# project.net
KiCad netlist of a schematic drawn in EAGLE
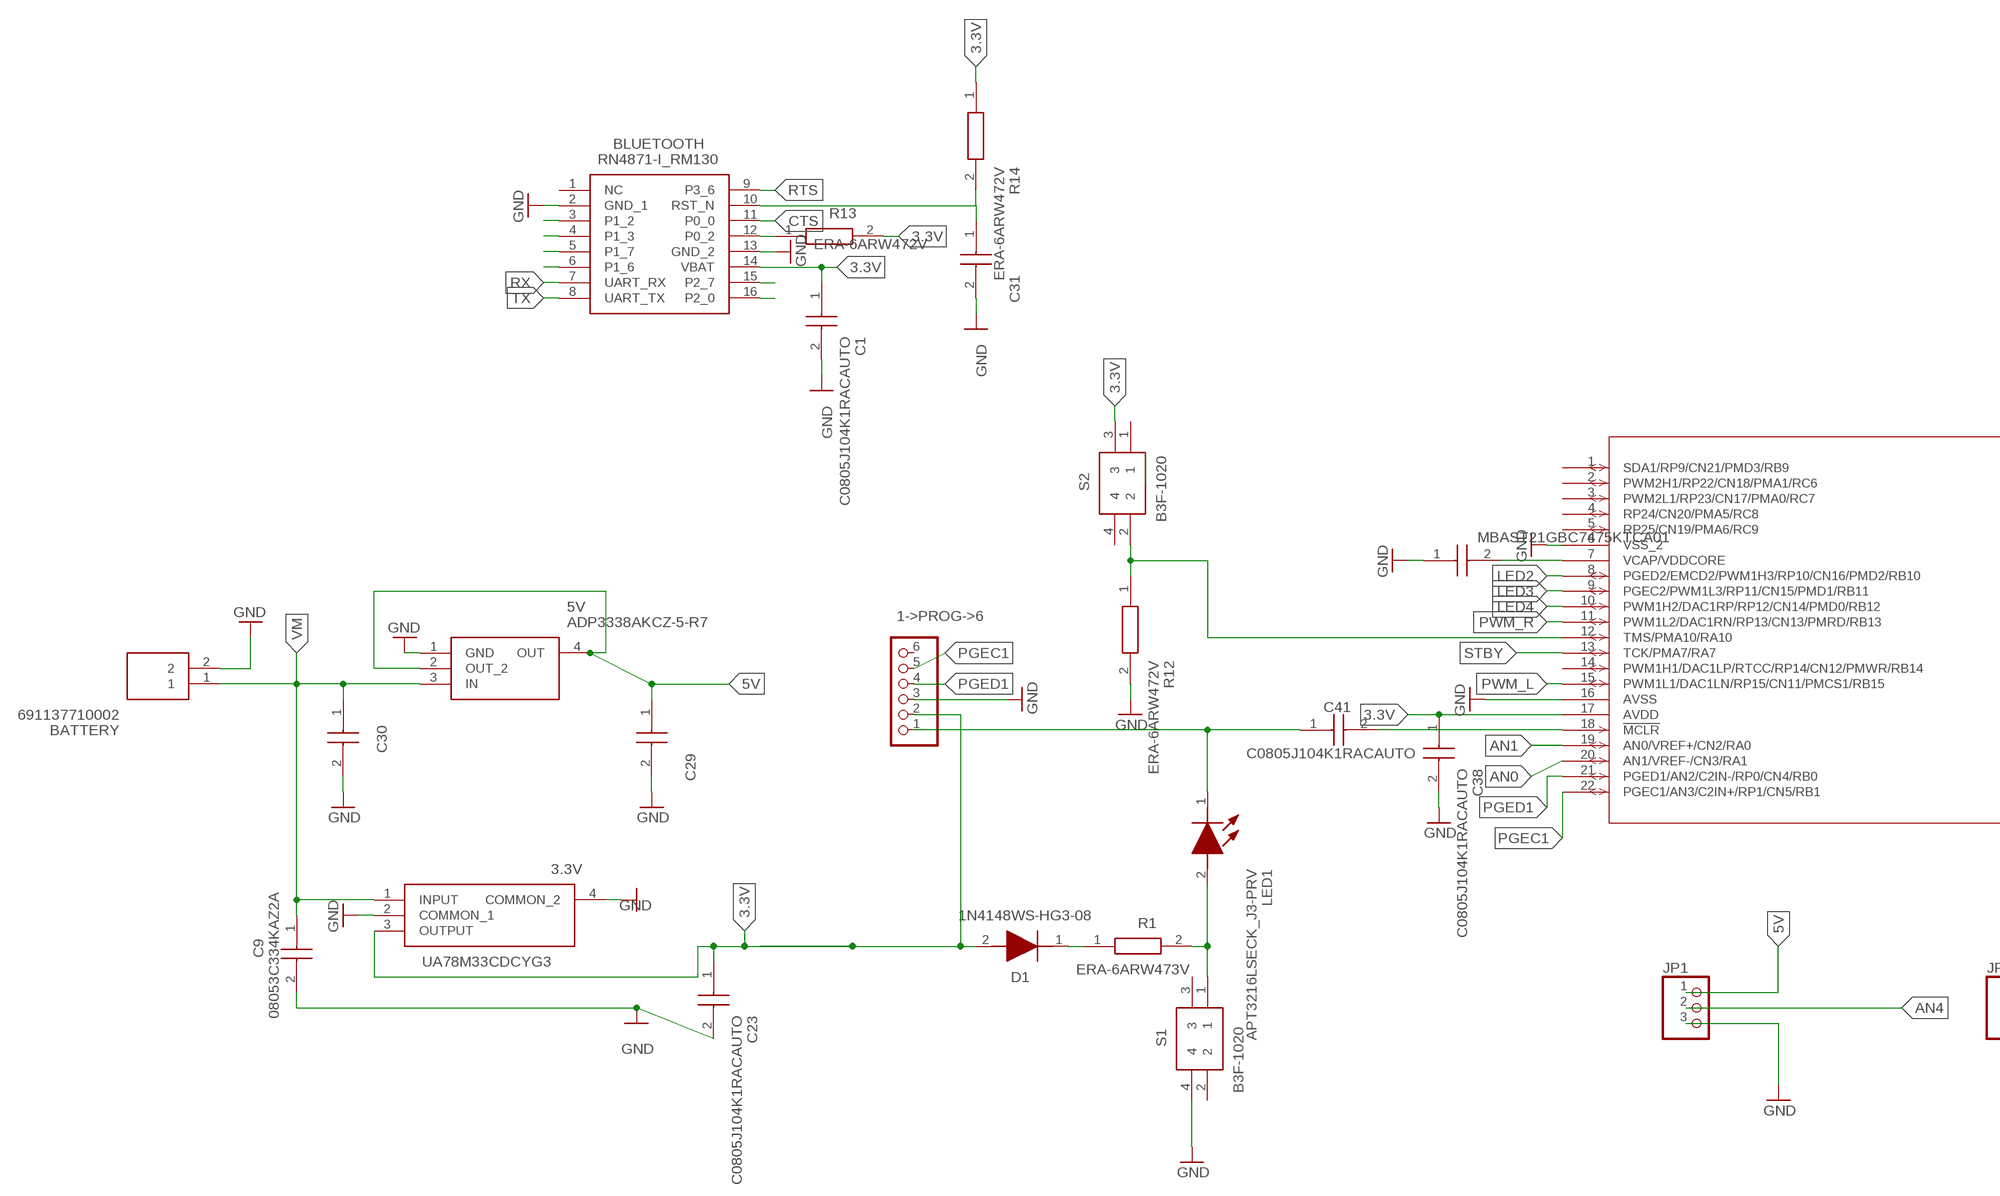
[diagram p0: schematic, sheet 1, part 1 of 2]
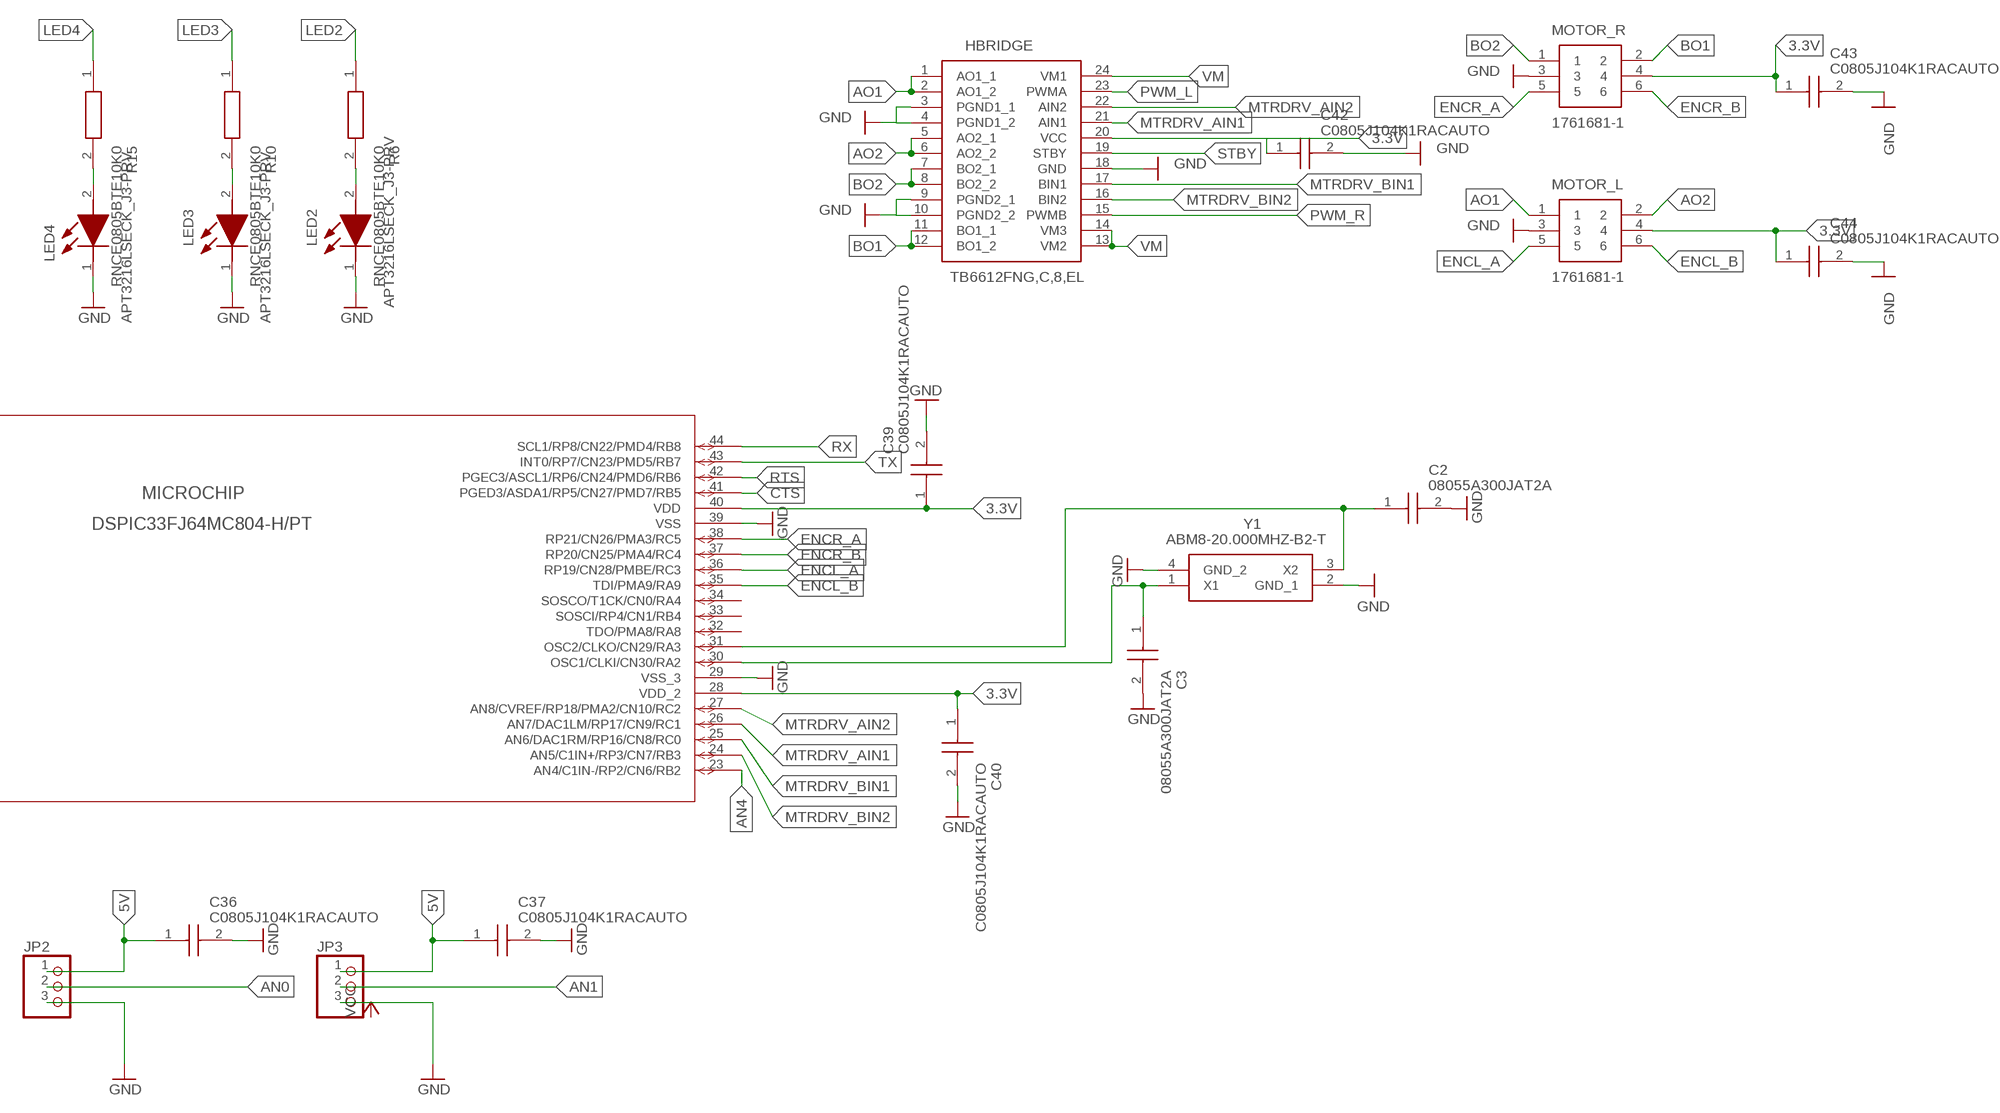
[diagram p1: schematic, sheet 1, part 2 of 2]

(export (version "E")
  (design (tool "Eeschema 10.0.6"))
  (components
    (comp (ref "1->PROG->6")
      (value "PINHD-1X6")
      (footprint "eagle-import:1X06")
      (libsource (lib "eagle-import") (part "PINHD-1X6"))
    )
    (comp (ref "3.3V")
      (value "UA78M33CDCYG3")
      (footprint "eagle-import:SOT230P700X180-4N")
      (fields (field (name "MOUSER_PART_NUMBER") "595-UA78M33CDCYG3"))
      (libsource (lib "eagle-import") (part "UA78M33CDCYG3"))
    )
    (comp (ref "5V")
      (value "ADP3338AKCZ-5-R7")
      (footprint "eagle-import:SOT230P700X180-4N")
      (fields (field (name "MOUSER_PART_NUMBER") "584-ADP3338AKCZ-5-R7"))
      (libsource (lib "eagle-import") (part "ADP3338AKCZ-5-R7"))
    )
    (comp (ref "BATTERY")
      (value "691137710002")
      (footprint "eagle-import:SHDR2W70P0X500_1X2_1000X750X11")
      (fields (field (name "MOUSER_PART_NUMBER") "710-691137710002"))
      (libsource (lib "eagle-import") (part "691137710002"))
    )
    (comp (ref "BLUETOOTH")
      (value "RN4871-I_RM130")
      (footprint "eagle-import:RN4871")
      (fields
        (field (name "MANUFACTURER_PART_NUMBER") "RN4871-I/RM130")
        (field (name "MOUSER_PART_NUMBER") "579-RN4871IRM130")
      )
      (libsource (lib "eagle-import") (part "RN4871-I_RM130"))
    )
    (comp (ref "C1")
      (value "C0805J104K1RACAUTO")
      (footprint "eagle-import:CAPC2012X140N")
      (libsource (lib "eagle-import") (part "C0805J104K1RACAUTO"))
    )
    (comp (ref "C2")
      (value "08055A300JAT2A")
      (footprint "eagle-import:CAPC2012X94N")
      (fields (field (name "MOUSER_PART_NUMBER") "581-08055A300J"))
      (libsource (lib "eagle-import") (part "08055A300JAT2A"))
    )
    (comp (ref "C3")
      (value "08055A300JAT2A")
      (footprint "eagle-import:CAPC2012X94N")
      (fields (field (name "MOUSER_PART_NUMBER") "581-08055A300J"))
      (libsource (lib "eagle-import") (part "08055A300JAT2A"))
    )
    (comp (ref "C4")
      (value "MBAST21GBC7475KTCA01")
      (footprint "eagle-import:CAPC2114X145N")
      (libsource (lib "eagle-import") (part "MBAST21GBC7475KTCA01"))
    )
    (comp (ref "C9")
      (value "08053C334KAZ2A")
      (footprint "eagle-import:CAPC2012X152N")
      (libsource (lib "eagle-import") (part "08053C334KAZ2A"))
    )
    (comp (ref "C23")
      (value "C0805J104K1RACAUTO")
      (footprint "eagle-import:CAPC2012X140N")
      (libsource (lib "eagle-import") (part "C0805J104K1RACAUTO"))
    )
    (comp (ref "C29")
      (value "C0805J104K1RACAUTO")
      (footprint "eagle-import:CAPC2012X140N")
      (libsource (lib "eagle-import") (part "C0805J104K1RACAUTO"))
    )
    (comp (ref "C30")
      (value "1µF")
      (footprint "eagle-import:CAPC2012X140N")
      (fields (field (name "MANUFACTURER_PART_NUMBER") "C0805J104K1RACAUTO"))
      (libsource (lib "eagle-import") (part "C0805J104K1RACAUTO"))
    )
    (comp (ref "C31")
      (value "C0805J104K1RACAUTO")
      (footprint "eagle-import:CAPC2012X140N")
      (libsource (lib "eagle-import") (part "C0805J104K1RACAUTO"))
    )
    (comp (ref "C36")
      (value "C0805J104K1RACAUTO")
      (footprint "eagle-import:CAPC2012X140N")
      (libsource (lib "eagle-import") (part "C0805J104K1RACAUTO"))
    )
    (comp (ref "C37")
      (value "C0805J104K1RACAUTO")
      (footprint "eagle-import:CAPC2012X140N")
      (libsource (lib "eagle-import") (part "C0805J104K1RACAUTO"))
    )
    (comp (ref "C38")
      (value "C0805J104K1RACAUTO")
      (footprint "eagle-import:CAPC2012X140N")
      (libsource (lib "eagle-import") (part "C0805J104K1RACAUTO"))
    )
    (comp (ref "C39")
      (value "C0805J104K1RACAUTO")
      (footprint "eagle-import:CAPC2012X140N")
      (libsource (lib "eagle-import") (part "C0805J104K1RACAUTO"))
    )
    (comp (ref "C40")
      (value "C0805J104K1RACAUTO")
      (footprint "eagle-import:CAPC2012X140N")
      (libsource (lib "eagle-import") (part "C0805J104K1RACAUTO"))
    )
    (comp (ref "C41")
      (value "C0805J104K1RACAUTO")
      (footprint "eagle-import:CAPC2012X140N")
      (libsource (lib "eagle-import") (part "C0805J104K1RACAUTO"))
    )
    (comp (ref "C42")
      (value "C0805J104K1RACAUTO")
      (footprint "eagle-import:CAPC2012X140N")
      (libsource (lib "eagle-import") (part "C0805J104K1RACAUTO"))
    )
    (comp (ref "C43")
      (value "C0805J104K1RACAUTO")
      (footprint "eagle-import:CAPC2012X140N")
      (libsource (lib "eagle-import") (part "C0805J104K1RACAUTO"))
    )
    (comp (ref "C44")
      (value "C0805J104K1RACAUTO")
      (footprint "eagle-import:CAPC2012X140N")
      (libsource (lib "eagle-import") (part "C0805J104K1RACAUTO"))
    )
    (comp (ref "D1")
      (value "1N4148WS-HG3-08")
      (footprint "eagle-import:SOD2713X115N")
      (fields (field (name "MOUSER_PART_NUMBER") "78-1N4148WS-HG3-08"))
      (libsource (lib "eagle-import") (part "1N4148WS-HG3-08"))
    )
    (comp (ref "HBRIDGE")
      (value "TB6612FNG,C,8,EL")
      (footprint "eagle-import:SOP65P760X160-24N")
      (fields (field (name "MOUSER_PART_NUMBER") "757-TB6612FNGC8EL"))
      (libsource (lib "eagle-import") (part "TB6612FNG,C,8,EL"))
    )
    (comp (ref "JP1")
      (value "PINHD-1X3")
      (footprint "eagle-import:1X03")
      (libsource (lib "eagle-import") (part "PINHD-1X3"))
    )
    (comp (ref "JP2")
      (value "PINHD-1X3")
      (footprint "eagle-import:1X03")
      (libsource (lib "eagle-import") (part "PINHD-1X3"))
    )
    (comp (ref "JP3")
      (value "PINHD-1X3")
      (footprint "eagle-import:1X03")
      (libsource (lib "eagle-import") (part "PINHD-1X3"))
    )
    (comp (ref "LED1")
      (value "APT3216LSECK_J3-PRV")
      (footprint "eagle-import:LEDC3216X95N")
      (fields
        (field (name "MANUFACTURER_PART_NUMBER") "APT3216LSECK/J3-PRV")
        (field (name "MOUSER_PART_NUMBER") "604-APT3216LSECKJ3RV")
      )
      (libsource (lib "eagle-import") (part "APT3216LSECK_J3-PRV"))
    )
    (comp (ref "LED2")
      (value "APT3216LSECK_J3-PRV")
      (footprint "eagle-import:LEDC3216X95N")
      (fields
        (field (name "MANUFACTURER_PART_NUMBER") "APT3216LSECK/J3-PRV")
        (field (name "MOUSER_PART_NUMBER") "604-APT3216LSECKJ3RV")
      )
      (libsource (lib "eagle-import") (part "APT3216LSECK_J3-PRV"))
    )
    (comp (ref "LED3")
      (value "APT3216LSECK_J3-PRV")
      (footprint "eagle-import:LEDC3216X95N")
      (fields
        (field (name "MANUFACTURER_PART_NUMBER") "APT3216LSECK/J3-PRV")
        (field (name "MOUSER_PART_NUMBER") "604-APT3216LSECKJ3RV")
      )
      (libsource (lib "eagle-import") (part "APT3216LSECK_J3-PRV"))
    )
    (comp (ref "LED4")
      (value "APT3216LSECK_J3-PRV")
      (footprint "eagle-import:LEDC3216X95N")
      (fields
        (field (name "MANUFACTURER_PART_NUMBER") "APT3216LSECK/J3-PRV")
        (field (name "MOUSER_PART_NUMBER") "604-APT3216LSECKJ3RV")
      )
      (libsource (lib "eagle-import") (part "APT3216LSECK_J3-PRV"))
    )
    (comp (ref "MICROCHIP")
      (value "DSPIC33FJ64MC804-H/PT")
      (footprint "eagle-import:TQFP44_10X10MC_MCH")
      (fields (field (name "COPYRIGHT") "Copyright (C) 2025 Ultra Librarian. All rights reserved."))
      (libsource (lib "eagle-import") (part "DSPIC33FJ64MC804-H/PT"))
    )
    (comp (ref "MOTOR_L")
      (value "1761681-1")
      (footprint "eagle-import:SHDR6W67P254_2X3_1524X916X922P")
      (fields (field (name "MOUSER_PART_NUMBER") "571-1761681-1"))
      (libsource (lib "eagle-import") (part "1761681-1"))
    )
    (comp (ref "MOTOR_R")
      (value "1761681-1")
      (footprint "eagle-import:SHDR6W67P254_2X3_1524X916X922P")
      (fields (field (name "MOUSER_PART_NUMBER") "571-1761681-1"))
      (libsource (lib "eagle-import") (part "1761681-1"))
    )
    (comp (ref "R1")
      (value "ERA-6ARW473V")
      (footprint "eagle-import:ERA6AEB101V")
      (fields (field (name "MOUSER_PART_NUMBER") "667-ERA-6ARW473V"))
      (libsource (lib "eagle-import") (part "ERA-6ARW473V"))
    )
    (comp (ref "R6")
      (value "RNCE0805BTE10K0")
      (footprint "eagle-import:RESC2012X65N")
      (libsource (lib "eagle-import") (part "RNCE0805BTE10K0"))
    )
    (comp (ref "R10")
      (value "RNCE0805BTE10K0")
      (footprint "eagle-import:RESC2012X65N")
      (libsource (lib "eagle-import") (part "RNCE0805BTE10K0"))
    )
    (comp (ref "R12")
      (value "ERA-6ARW472V")
      (footprint "eagle-import:ERA6AEB101V")
      (fields (field (name "MOUSER_PART_NUMBER") "667-ERA-6ARW472V"))
      (libsource (lib "eagle-import") (part "ERA-6ARW472V"))
    )
    (comp (ref "R13")
      (value "ERA-6ARW472V")
      (footprint "eagle-import:ERA6AEB101V")
      (fields (field (name "MOUSER_PART_NUMBER") "667-ERA-6ARW472V"))
      (libsource (lib "eagle-import") (part "ERA-6ARW472V"))
    )
    (comp (ref "R14")
      (value "ERA-6ARW472V")
      (footprint "eagle-import:ERA6AEB101V")
      (fields (field (name "MOUSER_PART_NUMBER") "667-ERA-6ARW472V"))
      (libsource (lib "eagle-import") (part "ERA-6ARW472V"))
    )
    (comp (ref "R15")
      (value "RNCE0805BTE10K0")
      (footprint "eagle-import:RESC2012X65N")
      (libsource (lib "eagle-import") (part "RNCE0805BTE10K0"))
    )
    (comp (ref "S1")
      (value "B3F-1020")
      (footprint "eagle-import:B3F1000")
      (fields (field (name "MOUSER_PART_NUMBER") "653-B3F-1020"))
      (libsource (lib "eagle-import") (part "B3F-1020"))
    )
    (comp (ref "S2")
      (value "B3F-1020")
      (footprint "eagle-import:B3F1000")
      (fields (field (name "MOUSER_PART_NUMBER") "653-B3F-1020"))
      (libsource (lib "eagle-import") (part "B3F-1020"))
    )
    (comp (ref "Y1")
      (value "ABM8-20.000MHZ-B2-T")
      (footprint "eagle-import:ABM810000MHZ12D2W")
      (fields (field (name "MOUSER_PART_NUMBER") "815-ABM8-20-B2-T"))
      (libsource (lib "eagle-import") (part "ABM8-20.000MHZ-B2-T"))
    )
  )
  (nets
    (net (code "1") (name "3.3V") (class "Default")
      (node (ref "1->PROG->6") (pin "2") (pinfunction "2_2") (pintype "passive"))
      (node (ref "3.3V") (pin "3") (pinfunction "OUTPUT_3") (pintype "bidirectional"))
      (node (ref "BLUETOOTH") (pin "14") (pinfunction "VBAT_14") (pintype "bidirectional"))
      (node (ref "C1") (pin "1") (pinfunction "1_1") (pintype "bidirectional"))
      (node (ref "C23") (pin "1") (pinfunction "1_1") (pintype "bidirectional"))
      (node (ref "C38") (pin "1") (pinfunction "1_1") (pintype "bidirectional"))
      (node (ref "C39") (pin "1") (pinfunction "1_1") (pintype "bidirectional"))
      (node (ref "C40") (pin "1") (pinfunction "1_1") (pintype "bidirectional"))
      (node (ref "C42") (pin "1") (pinfunction "1_1") (pintype "bidirectional"))
      (node (ref "C43") (pin "1") (pinfunction "1_1") (pintype "bidirectional"))
      (node (ref "C44") (pin "1") (pinfunction "1_1") (pintype "bidirectional"))
      (node (ref "D1") (pin "2") (pinfunction "A_2") (pintype "bidirectional"))
      (node (ref "HBRIDGE") (pin "20") (pinfunction "VCC_20") (pintype "bidirectional"))
      (node (ref "MICROCHIP") (pin "17") (pinfunction "AVDD_17") (pintype "power_in"))
      (node (ref "MICROCHIP") (pin "28") (pinfunction "VDD_2_28") (pintype "power_in"))
      (node (ref "MICROCHIP") (pin "40") (pinfunction "VDD_40") (pintype "power_in"))
      (node (ref "MOTOR_L") (pin "4") (pinfunction "4_4") (pintype "bidirectional"))
      (node (ref "MOTOR_R") (pin "4") (pinfunction "4_4") (pintype "bidirectional"))
      (node (ref "R13") (pin "2") (pinfunction "2_2") (pintype "bidirectional"))
      (node (ref "R14") (pin "1") (pinfunction "1_1") (pintype "bidirectional"))
      (node (ref "S2") (pin "3") (pinfunction "3_3") (pintype "bidirectional"))
    )
    (net (code "2") (name "5V") (class "Default")
      (node (ref "5V") (pin "2") (pinfunction "OUT_2_2") (pintype "bidirectional"))
      (node (ref "5V") (pin "4") (pinfunction "OUT_4") (pintype "bidirectional"))
      (node (ref "C29") (pin "1") (pinfunction "1_1") (pintype "bidirectional"))
      (node (ref "C36") (pin "1") (pinfunction "1_1") (pintype "bidirectional"))
      (node (ref "C37") (pin "1") (pinfunction "1_1") (pintype "bidirectional"))
      (node (ref "JP1") (pin "1") (pinfunction "1_1") (pintype "passive"))
      (node (ref "JP2") (pin "1") (pinfunction "1_1") (pintype "passive"))
      (node (ref "JP3") (pin "1") (pinfunction "1_1") (pintype "passive"))
    )
    (net (code "3") (name "AN0") (class "Default")
      (node (ref "JP2") (pin "2") (pinfunction "2_2") (pintype "passive"))
      (node (ref "MICROCHIP") (pin "20") (pinfunction "AN1/VREF-/CN3/RA1_20") (pintype "bidirectional"))
    )
    (net (code "4") (name "AN1") (class "Default")
      (node (ref "JP3") (pin "2") (pinfunction "2_2") (pintype "passive"))
      (node (ref "MICROCHIP") (pin "19") (pinfunction "AN0/VREF+/CN2/RA0_19") (pintype "bidirectional"))
    )
    (net (code "5") (name "AN4") (class "Default")
      (node (ref "JP1") (pin "2") (pinfunction "2_2") (pintype "passive"))
      (node (ref "MICROCHIP") (pin "23") (pinfunction "AN4/C1IN-/RP2/CN6/RB2_23") (pintype "bidirectional"))
    )
    (net (code "6") (name "AO1") (class "Default")
      (node (ref "HBRIDGE") (pin "1") (pinfunction "AO1_1_1") (pintype "bidirectional"))
      (node (ref "HBRIDGE") (pin "2") (pinfunction "AO1_2_2") (pintype "bidirectional"))
      (node (ref "MOTOR_L") (pin "1") (pinfunction "1_1") (pintype "bidirectional"))
    )
    (net (code "7") (name "AO2") (class "Default")
      (node (ref "HBRIDGE") (pin "5") (pinfunction "AO2_1_5") (pintype "bidirectional"))
      (node (ref "HBRIDGE") (pin "6") (pinfunction "AO2_2_6") (pintype "bidirectional"))
      (node (ref "MOTOR_L") (pin "2") (pinfunction "2_2") (pintype "bidirectional"))
    )
    (net (code "8") (name "BO1") (class "Default")
      (node (ref "HBRIDGE") (pin "11") (pinfunction "BO1_1_11") (pintype "bidirectional"))
      (node (ref "HBRIDGE") (pin "12") (pinfunction "BO1_2_12") (pintype "bidirectional"))
      (node (ref "MOTOR_R") (pin "2") (pinfunction "2_2") (pintype "bidirectional"))
    )
    (net (code "9") (name "BO2") (class "Default")
      (node (ref "HBRIDGE") (pin "7") (pinfunction "BO2_1_7") (pintype "bidirectional"))
      (node (ref "HBRIDGE") (pin "8") (pinfunction "BO2_2_8") (pintype "bidirectional"))
      (node (ref "MOTOR_R") (pin "1") (pinfunction "1_1") (pintype "bidirectional"))
    )
    (net (code "10") (name "CTS") (class "Default")
      (node (ref "BLUETOOTH") (pin "11") (pinfunction "P0_0_11") (pintype "bidirectional"))
      (node (ref "MICROCHIP") (pin "41") (pinfunction "PGED3/ASDA1/RP5/CN27/PMD7/RB5_41") (pintype "bidirectional"))
    )
    (net (code "11") (name "ENCL_A") (class "Default")
      (node (ref "MICROCHIP") (pin "36") (pinfunction "RP19/CN28/PMBE/RC3_36") (pintype "bidirectional"))
      (node (ref "MOTOR_L") (pin "5") (pinfunction "5_5") (pintype "bidirectional"))
    )
    (net (code "12") (name "ENCL_B") (class "Default")
      (node (ref "MICROCHIP") (pin "35") (pinfunction "TDI/PMA9/RA9_35") (pintype "bidirectional"))
      (node (ref "MOTOR_L") (pin "6") (pinfunction "6_6") (pintype "bidirectional"))
    )
    (net (code "13") (name "ENCR_A") (class "Default")
      (node (ref "MICROCHIP") (pin "38") (pinfunction "RP21/CN26/PMA3/RC5_38") (pintype "bidirectional"))
      (node (ref "MOTOR_R") (pin "5") (pinfunction "5_5") (pintype "bidirectional"))
    )
    (net (code "14") (name "ENCR_B") (class "Default")
      (node (ref "MICROCHIP") (pin "37") (pinfunction "RP20/CN25/PMA4/RC4_37") (pintype "bidirectional"))
      (node (ref "MOTOR_R") (pin "6") (pinfunction "6_6") (pintype "bidirectional"))
    )
    (net (code "15") (name "GND") (class "Default")
      (node (ref "1->PROG->6") (pin "3") (pinfunction "3_3") (pintype "passive"))
      (node (ref "3.3V") (pin "2") (pinfunction "COMMON_1_2") (pintype "bidirectional"))
      (node (ref "3.3V") (pin "4") (pinfunction "COMMON_2_4") (pintype "bidirectional"))
      (node (ref "5V") (pin "1") (pinfunction "GND_1") (pintype "bidirectional"))
      (node (ref "BATTERY") (pin "2") (pinfunction "2_2") (pintype "bidirectional"))
      (node (ref "BLUETOOTH") (pin "13") (pinfunction "GND_2_13") (pintype "bidirectional"))
      (node (ref "BLUETOOTH") (pin "2") (pinfunction "GND_1_2") (pintype "bidirectional"))
      (node (ref "C1") (pin "2") (pinfunction "2_2") (pintype "bidirectional"))
      (node (ref "C2") (pin "2") (pinfunction "2_2") (pintype "bidirectional"))
      (node (ref "C23") (pin "2") (pinfunction "2_2") (pintype "bidirectional"))
      (node (ref "C29") (pin "2") (pinfunction "2_2") (pintype "bidirectional"))
      (node (ref "C3") (pin "2") (pinfunction "2_2") (pintype "bidirectional"))
      (node (ref "C30") (pin "2") (pinfunction "2_2") (pintype "bidirectional"))
      (node (ref "C31") (pin "2") (pinfunction "2_2") (pintype "bidirectional"))
      (node (ref "C36") (pin "2") (pinfunction "2_2") (pintype "bidirectional"))
      (node (ref "C37") (pin "2") (pinfunction "2_2") (pintype "bidirectional"))
      (node (ref "C38") (pin "2") (pinfunction "2_2") (pintype "bidirectional"))
      (node (ref "C39") (pin "2") (pinfunction "2_2") (pintype "bidirectional"))
      (node (ref "C4") (pin "1") (pinfunction "1_1") (pintype "bidirectional"))
      (node (ref "C40") (pin "2") (pinfunction "2_2") (pintype "bidirectional"))
      (node (ref "C42") (pin "2") (pinfunction "2_2") (pintype "bidirectional"))
      (node (ref "C43") (pin "2") (pinfunction "2_2") (pintype "bidirectional"))
      (node (ref "C44") (pin "2") (pinfunction "2_2") (pintype "bidirectional"))
      (node (ref "C9") (pin "2") (pinfunction "2_2") (pintype "bidirectional"))
      (node (ref "HBRIDGE") (pin "10") (pinfunction "PGND2_2_10") (pintype "bidirectional"))
      (node (ref "HBRIDGE") (pin "18") (pinfunction "GND_18") (pintype "bidirectional"))
      (node (ref "HBRIDGE") (pin "3") (pinfunction "PGND1_1_3") (pintype "bidirectional"))
      (node (ref "HBRIDGE") (pin "4") (pinfunction "PGND1_2_4") (pintype "bidirectional"))
      (node (ref "HBRIDGE") (pin "9") (pinfunction "PGND2_1_9") (pintype "bidirectional"))
      (node (ref "JP1") (pin "3") (pinfunction "3_3") (pintype "passive"))
      (node (ref "JP2") (pin "3") (pinfunction "3_3") (pintype "passive"))
      (node (ref "JP3") (pin "3") (pinfunction "3_3") (pintype "passive"))
      (node (ref "LED2") (pin "1") (pinfunction "K_1") (pintype "bidirectional"))
      (node (ref "LED3") (pin "1") (pinfunction "K_1") (pintype "bidirectional"))
      (node (ref "LED4") (pin "1") (pinfunction "K_1") (pintype "bidirectional"))
      (node (ref "MICROCHIP") (pin "16") (pinfunction "AVSS_16") (pintype "power_in"))
      (node (ref "MICROCHIP") (pin "29") (pinfunction "VSS_3_29") (pintype "power_in"))
      (node (ref "MICROCHIP") (pin "39") (pinfunction "VSS_39") (pintype "power_in"))
      (node (ref "MICROCHIP") (pin "6") (pinfunction "VSS_2_6") (pintype "power_in"))
      (node (ref "MOTOR_L") (pin "3") (pinfunction "3_3") (pintype "bidirectional"))
      (node (ref "MOTOR_R") (pin "3") (pinfunction "3_3") (pintype "bidirectional"))
      (node (ref "R12") (pin "2") (pinfunction "2_2") (pintype "bidirectional"))
      (node (ref "S1") (pin "4") (pinfunction "4_4") (pintype "bidirectional"))
      (node (ref "Y1") (pin "2") (pinfunction "GND_1_2") (pintype "bidirectional"))
      (node (ref "Y1") (pin "4") (pinfunction "GND_2_4") (pintype "bidirectional"))
    )
    (net (code "16") (name "LED2") (class "Default")
      (node (ref "MICROCHIP") (pin "8") (pinfunction "PGED2/EMCD2/PWM1H3/RP10/CN16/PMD2/RB10_8") (pintype "bidirectional"))
      (node (ref "R6") (pin "1") (pinfunction "1_1") (pintype "bidirectional"))
    )
    (net (code "17") (name "LED3") (class "Default")
      (node (ref "MICROCHIP") (pin "9") (pinfunction "PGEC2/PWM1L3/RP11/CN15/PMD1/RB11_9") (pintype "bidirectional"))
      (node (ref "R10") (pin "1") (pinfunction "1_1") (pintype "bidirectional"))
    )
    (net (code "18") (name "LED4") (class "Default")
      (node (ref "MICROCHIP") (pin "10") (pinfunction "PWM1H2/DAC1RP/RP12/CN14/PMD0/RB12_10") (pintype "bidirectional"))
      (node (ref "R15") (pin "1") (pinfunction "1_1") (pintype "bidirectional"))
    )
    (net (code "19") (name "MTRDRV_AIN1") (class "Default")
      (node (ref "HBRIDGE") (pin "21") (pinfunction "AIN1_21") (pintype "bidirectional"))
      (node (ref "MICROCHIP") (pin "26") (pinfunction "AN7/DAC1LM/RP17/CN9/RC1_26") (pintype "bidirectional"))
    )
    (net (code "20") (name "MTRDRV_AIN2") (class "Default")
      (node (ref "HBRIDGE") (pin "22") (pinfunction "AIN2_22") (pintype "bidirectional"))
      (node (ref "MICROCHIP") (pin "27") (pinfunction "AN8/CVREF/RP18/PMA2/CN10/RC2_27") (pintype "bidirectional"))
    )
    (net (code "21") (name "MTRDRV_BIN1") (class "Default")
      (node (ref "HBRIDGE") (pin "17") (pinfunction "BIN1_17") (pintype "bidirectional"))
      (node (ref "MICROCHIP") (pin "25") (pinfunction "AN6/DAC1RM/RP16/CN8/RC0_25") (pintype "bidirectional"))
    )
    (net (code "22") (name "MTRDRV_BIN2") (class "Default")
      (node (ref "HBRIDGE") (pin "16") (pinfunction "BIN2_16") (pintype "bidirectional"))
      (node (ref "MICROCHIP") (pin "24") (pinfunction "AN5/C1IN+/RP3/CN7/RB3_24") (pintype "bidirectional"))
    )
    (net (code "23") (name "Net-(BLUETOOTH-P0_2)") (class "Default")
      (node (ref "BLUETOOTH") (pin "12") (pinfunction "P0_2_12") (pintype "bidirectional"))
      (node (ref "R13") (pin "1") (pinfunction "1_1") (pintype "bidirectional"))
    )
    (net (code "24") (name "Net-(BLUETOOTH-RST_N)") (class "Default")
      (node (ref "BLUETOOTH") (pin "10") (pinfunction "RST_N_10") (pintype "bidirectional"))
      (node (ref "C31") (pin "1") (pinfunction "1_1") (pintype "bidirectional"))
      (node (ref "R14") (pin "2") (pinfunction "2_2") (pintype "bidirectional"))
    )
    (net (code "25") (name "Net-(D1-K)") (class "Default")
      (node (ref "D1") (pin "1") (pinfunction "K_1") (pintype "bidirectional"))
      (node (ref "R1") (pin "1") (pinfunction "1_1") (pintype "bidirectional"))
    )
    (net (code "26") (name "Net-(LED1-A)") (class "Default")
      (node (ref "LED1") (pin "2") (pinfunction "A_2") (pintype "bidirectional"))
      (node (ref "R1") (pin "2") (pinfunction "2_2") (pintype "bidirectional"))
      (node (ref "S1") (pin "1") (pinfunction "1_1") (pintype "bidirectional"))
    )
    (net (code "27") (name "Net-(LED1-K)") (class "Default")
      (node (ref "1->PROG->6") (pin "1") (pinfunction "1_1") (pintype "passive"))
      (node (ref "C41") (pin "1") (pinfunction "1_1") (pintype "bidirectional"))
      (node (ref "LED1") (pin "1") (pinfunction "K_1") (pintype "bidirectional"))
    )
    (net (code "28") (name "Net-(LED2-A)") (class "Default")
      (node (ref "LED2") (pin "2") (pinfunction "A_2") (pintype "bidirectional"))
      (node (ref "R6") (pin "2") (pinfunction "2_2") (pintype "bidirectional"))
    )
    (net (code "29") (name "Net-(LED3-A)") (class "Default")
      (node (ref "LED3") (pin "2") (pinfunction "A_2") (pintype "bidirectional"))
      (node (ref "R10") (pin "2") (pinfunction "2_2") (pintype "bidirectional"))
    )
    (net (code "30") (name "Net-(LED4-A)") (class "Default")
      (node (ref "LED4") (pin "2") (pinfunction "A_2") (pintype "bidirectional"))
      (node (ref "R15") (pin "2") (pinfunction "2_2") (pintype "bidirectional"))
    )
    (net (code "31") (name "Net-(MICROCHIP-OSC1{slash}CLKI{slash}CN30{slash}RA2)") (class "Default")
      (node (ref "C3") (pin "1") (pinfunction "1_1") (pintype "bidirectional"))
      (node (ref "MICROCHIP") (pin "30") (pinfunction "OSC1/CLKI/CN30/RA2_30") (pintype "bidirectional"))
      (node (ref "Y1") (pin "1") (pinfunction "X1_1") (pintype "bidirectional"))
    )
    (net (code "32") (name "Net-(MICROCHIP-OSC2{slash}CLKO{slash}CN29{slash}RA3)") (class "Default")
      (node (ref "C2") (pin "1") (pinfunction "1_1") (pintype "bidirectional"))
      (node (ref "MICROCHIP") (pin "31") (pinfunction "OSC2/CLKO/CN29/RA3_31") (pintype "bidirectional"))
      (node (ref "Y1") (pin "3") (pinfunction "X2_3") (pintype "bidirectional"))
    )
    (net (code "33") (name "Net-(MICROCHIP-TMS{slash}PMA10{slash}RA10)") (class "Default")
      (node (ref "MICROCHIP") (pin "12") (pinfunction "TMS/PMA10/RA10_12") (pintype "bidirectional"))
      (node (ref "R12") (pin "1") (pinfunction "1_1") (pintype "bidirectional"))
      (node (ref "S2") (pin "2") (pinfunction "2_2") (pintype "bidirectional"))
    )
    (net (code "34") (name "Net-(MICROCHIP-VCAP{slash}VDDCORE)") (class "Default")
      (node (ref "C4") (pin "2") (pinfunction "2_2") (pintype "bidirectional"))
      (node (ref "MICROCHIP") (pin "7") (pinfunction "VCAP/VDDCORE_7") (pintype "power_in"))
    )
    (net (code "35") (name "Net-(MICROCHIP-~{MCLR})") (class "Default")
      (node (ref "C41") (pin "2") (pinfunction "2_2") (pintype "bidirectional"))
      (node (ref "MICROCHIP") (pin "18") (pinfunction "~{MCLR}_18") (pintype "input"))
    )
    (net (code "36") (name "PGEC1") (class "Default")
      (node (ref "1->PROG->6") (pin "5") (pinfunction "5_5") (pintype "passive"))
      (node (ref "MICROCHIP") (pin "22") (pinfunction "PGEC1/AN3/C2IN+/RP1/CN5/RB1_22") (pintype "bidirectional"))
    )
    (net (code "37") (name "PGED1") (class "Default")
      (node (ref "1->PROG->6") (pin "4") (pinfunction "4_4") (pintype "passive"))
      (node (ref "MICROCHIP") (pin "21") (pinfunction "PGED1/AN2/C2IN-/RP0/CN4/RB0_21") (pintype "bidirectional"))
    )
    (net (code "38") (name "PWM_L") (class "Default")
      (node (ref "HBRIDGE") (pin "23") (pinfunction "PWMA_23") (pintype "bidirectional"))
      (node (ref "MICROCHIP") (pin "15") (pinfunction "PWM1L1/DAC1LN/RP15/CN11/PMCS1/RB15_15") (pintype "bidirectional"))
    )
    (net (code "39") (name "PWM_R") (class "Default")
      (node (ref "HBRIDGE") (pin "15") (pinfunction "PWMB_15") (pintype "bidirectional"))
      (node (ref "MICROCHIP") (pin "11") (pinfunction "PWM1L2/DAC1RN/RP13/CN13/PMRD/RB13_11") (pintype "bidirectional"))
    )
    (net (code "40") (name "RTS") (class "Default")
      (node (ref "BLUETOOTH") (pin "9") (pinfunction "P3_6_9") (pintype "bidirectional"))
      (node (ref "MICROCHIP") (pin "42") (pinfunction "PGEC3/ASCL1/RP6/CN24/PMD6/RB6_42") (pintype "bidirectional"))
    )
    (net (code "41") (name "RX") (class "Default")
      (node (ref "BLUETOOTH") (pin "7") (pinfunction "UART_RX_7") (pintype "bidirectional"))
      (node (ref "MICROCHIP") (pin "44") (pinfunction "SCL1/RP8/CN22/PMD4/RB8_44") (pintype "bidirectional"))
    )
    (net (code "42") (name "STBY") (class "Default")
      (node (ref "HBRIDGE") (pin "19") (pinfunction "STBY_19") (pintype "bidirectional"))
      (node (ref "MICROCHIP") (pin "13") (pinfunction "TCK/PMA7/RA7_13") (pintype "bidirectional"))
    )
    (net (code "43") (name "TX") (class "Default")
      (node (ref "BLUETOOTH") (pin "8") (pinfunction "UART_TX_8") (pintype "bidirectional"))
      (node (ref "MICROCHIP") (pin "43") (pinfunction "INT0/RP7/CN23/PMD5/RB7_43") (pintype "bidirectional"))
    )
    (net (code "45") (name "VM") (class "Default")
      (node (ref "3.3V") (pin "1") (pinfunction "INPUT_1") (pintype "bidirectional"))
      (node (ref "5V") (pin "3") (pinfunction "IN_3") (pintype "bidirectional"))
      (node (ref "BATTERY") (pin "1") (pinfunction "1_1") (pintype "bidirectional"))
      (node (ref "C30") (pin "1") (pinfunction "1_1") (pintype "bidirectional"))
      (node (ref "C9") (pin "1") (pinfunction "1_1") (pintype "bidirectional"))
      (node (ref "HBRIDGE") (pin "13") (pinfunction "VM2_13") (pintype "bidirectional"))
      (node (ref "HBRIDGE") (pin "14") (pinfunction "VM3_14") (pintype "bidirectional"))
      (node (ref "HBRIDGE") (pin "24") (pinfunction "VM1_24") (pintype "bidirectional"))
    )
    (net (code "46") (name "unconnected-(1->PROG->6-Pad6)") (class "Default")
      (node (ref "1->PROG->6") (pin "6") (pinfunction "6_6") (pintype "passive"))
    )
    (net (code "47") (name "unconnected-(BLUETOOTH-NC-Pad1)") (class "Default")
      (node (ref "BLUETOOTH") (pin "1") (pinfunction "NC_1") (pintype "no_connect"))
    )
    (net (code "48") (name "unconnected-(BLUETOOTH-P1_2-Pad3)") (class "Default")
      (node (ref "BLUETOOTH") (pin "3") (pinfunction "P1_2_3") (pintype "bidirectional"))
    )
    (net (code "49") (name "unconnected-(BLUETOOTH-P1_3-Pad4)") (class "Default")
      (node (ref "BLUETOOTH") (pin "4") (pinfunction "P1_3_4") (pintype "bidirectional"))
    )
    (net (code "50") (name "unconnected-(BLUETOOTH-P1_6-Pad6)") (class "Default")
      (node (ref "BLUETOOTH") (pin "6") (pinfunction "P1_6_6") (pintype "bidirectional"))
    )
    (net (code "51") (name "unconnected-(BLUETOOTH-P1_7-Pad5)") (class "Default")
      (node (ref "BLUETOOTH") (pin "5") (pinfunction "P1_7_5") (pintype "bidirectional"))
    )
    (net (code "52") (name "unconnected-(BLUETOOTH-P2_0-Pad16)") (class "Default")
      (node (ref "BLUETOOTH") (pin "16") (pinfunction "P2_0_16") (pintype "bidirectional"))
    )
    (net (code "53") (name "unconnected-(BLUETOOTH-P2_7-Pad15)") (class "Default")
      (node (ref "BLUETOOTH") (pin "15") (pinfunction "P2_7_15") (pintype "bidirectional"))
    )
    (net (code "54") (name "unconnected-(MICROCHIP-PWM1H1{slash}DAC1LP{slash}RTCC{slash}RP14{slash}CN12{slash}PMWR{slash}RB14-Pad14)") (class "Default")
      (node (ref "MICROCHIP") (pin "14") (pinfunction "PWM1H1/DAC1LP/RTCC/RP14/CN12/PMWR/RB14_14") (pintype "bidirectional"))
    )
    (net (code "55") (name "unconnected-(MICROCHIP-PWM2H1{slash}RP22{slash}CN18{slash}PMA1{slash}RC6-Pad2)") (class "Default")
      (node (ref "MICROCHIP") (pin "2") (pinfunction "PWM2H1/RP22/CN18/PMA1/RC6_2") (pintype "bidirectional"))
    )
    (net (code "56") (name "unconnected-(MICROCHIP-PWM2L1{slash}RP23{slash}CN17{slash}PMA0{slash}RC7-Pad3)") (class "Default")
      (node (ref "MICROCHIP") (pin "3") (pinfunction "PWM2L1/RP23/CN17/PMA0/RC7_3") (pintype "bidirectional"))
    )
    (net (code "57") (name "unconnected-(MICROCHIP-RP24{slash}CN20{slash}PMA5{slash}RC8-Pad4)") (class "Default")
      (node (ref "MICROCHIP") (pin "4") (pinfunction "RP24/CN20/PMA5/RC8_4") (pintype "bidirectional"))
    )
    (net (code "58") (name "unconnected-(MICROCHIP-RP25{slash}CN19{slash}PMA6{slash}RC9-Pad5)") (class "Default")
      (node (ref "MICROCHIP") (pin "5") (pinfunction "RP25/CN19/PMA6/RC9_5") (pintype "bidirectional"))
    )
    (net (code "59") (name "unconnected-(MICROCHIP-SDA1{slash}RP9{slash}CN21{slash}PMD3{slash}RB9-Pad1)") (class "Default")
      (node (ref "MICROCHIP") (pin "1") (pinfunction "SDA1/RP9/CN21/PMD3/RB9_1") (pintype "bidirectional"))
    )
    (net (code "60") (name "unconnected-(MICROCHIP-SOSCI{slash}RP4{slash}CN1{slash}RB4-Pad33)") (class "Default")
      (node (ref "MICROCHIP") (pin "33") (pinfunction "SOSCI/RP4/CN1/RB4_33") (pintype "bidirectional"))
    )
    (net (code "61") (name "unconnected-(MICROCHIP-SOSCO{slash}T1CK{slash}CN0{slash}RA4-Pad34)") (class "Default")
      (node (ref "MICROCHIP") (pin "34") (pinfunction "SOSCO/T1CK/CN0/RA4_34") (pintype "bidirectional"))
    )
    (net (code "62") (name "unconnected-(MICROCHIP-TDO{slash}PMA8{slash}RA8-Pad32)") (class "Default")
      (node (ref "MICROCHIP") (pin "32") (pinfunction "TDO/PMA8/RA8_32") (pintype "bidirectional"))
    )
    (net (code "63") (name "unconnected-(S1-Pad2)") (class "Default")
      (node (ref "S1") (pin "2") (pinfunction "2_2") (pintype "bidirectional"))
    )
    (net (code "64") (name "unconnected-(S1-Pad3)") (class "Default")
      (node (ref "S1") (pin "3") (pinfunction "3_3") (pintype "bidirectional"))
    )
    (net (code "65") (name "unconnected-(S2-Pad1)") (class "Default")
      (node (ref "S2") (pin "1") (pinfunction "1_1") (pintype "bidirectional"))
    )
    (net (code "66") (name "unconnected-(S2-Pad4)") (class "Default")
      (node (ref "S2") (pin "4") (pinfunction "4_4") (pintype "bidirectional"))
    )
  )
)
